# 1604_lora_rak811.net
KiCad netlist of a schematic drawn in EAGLE
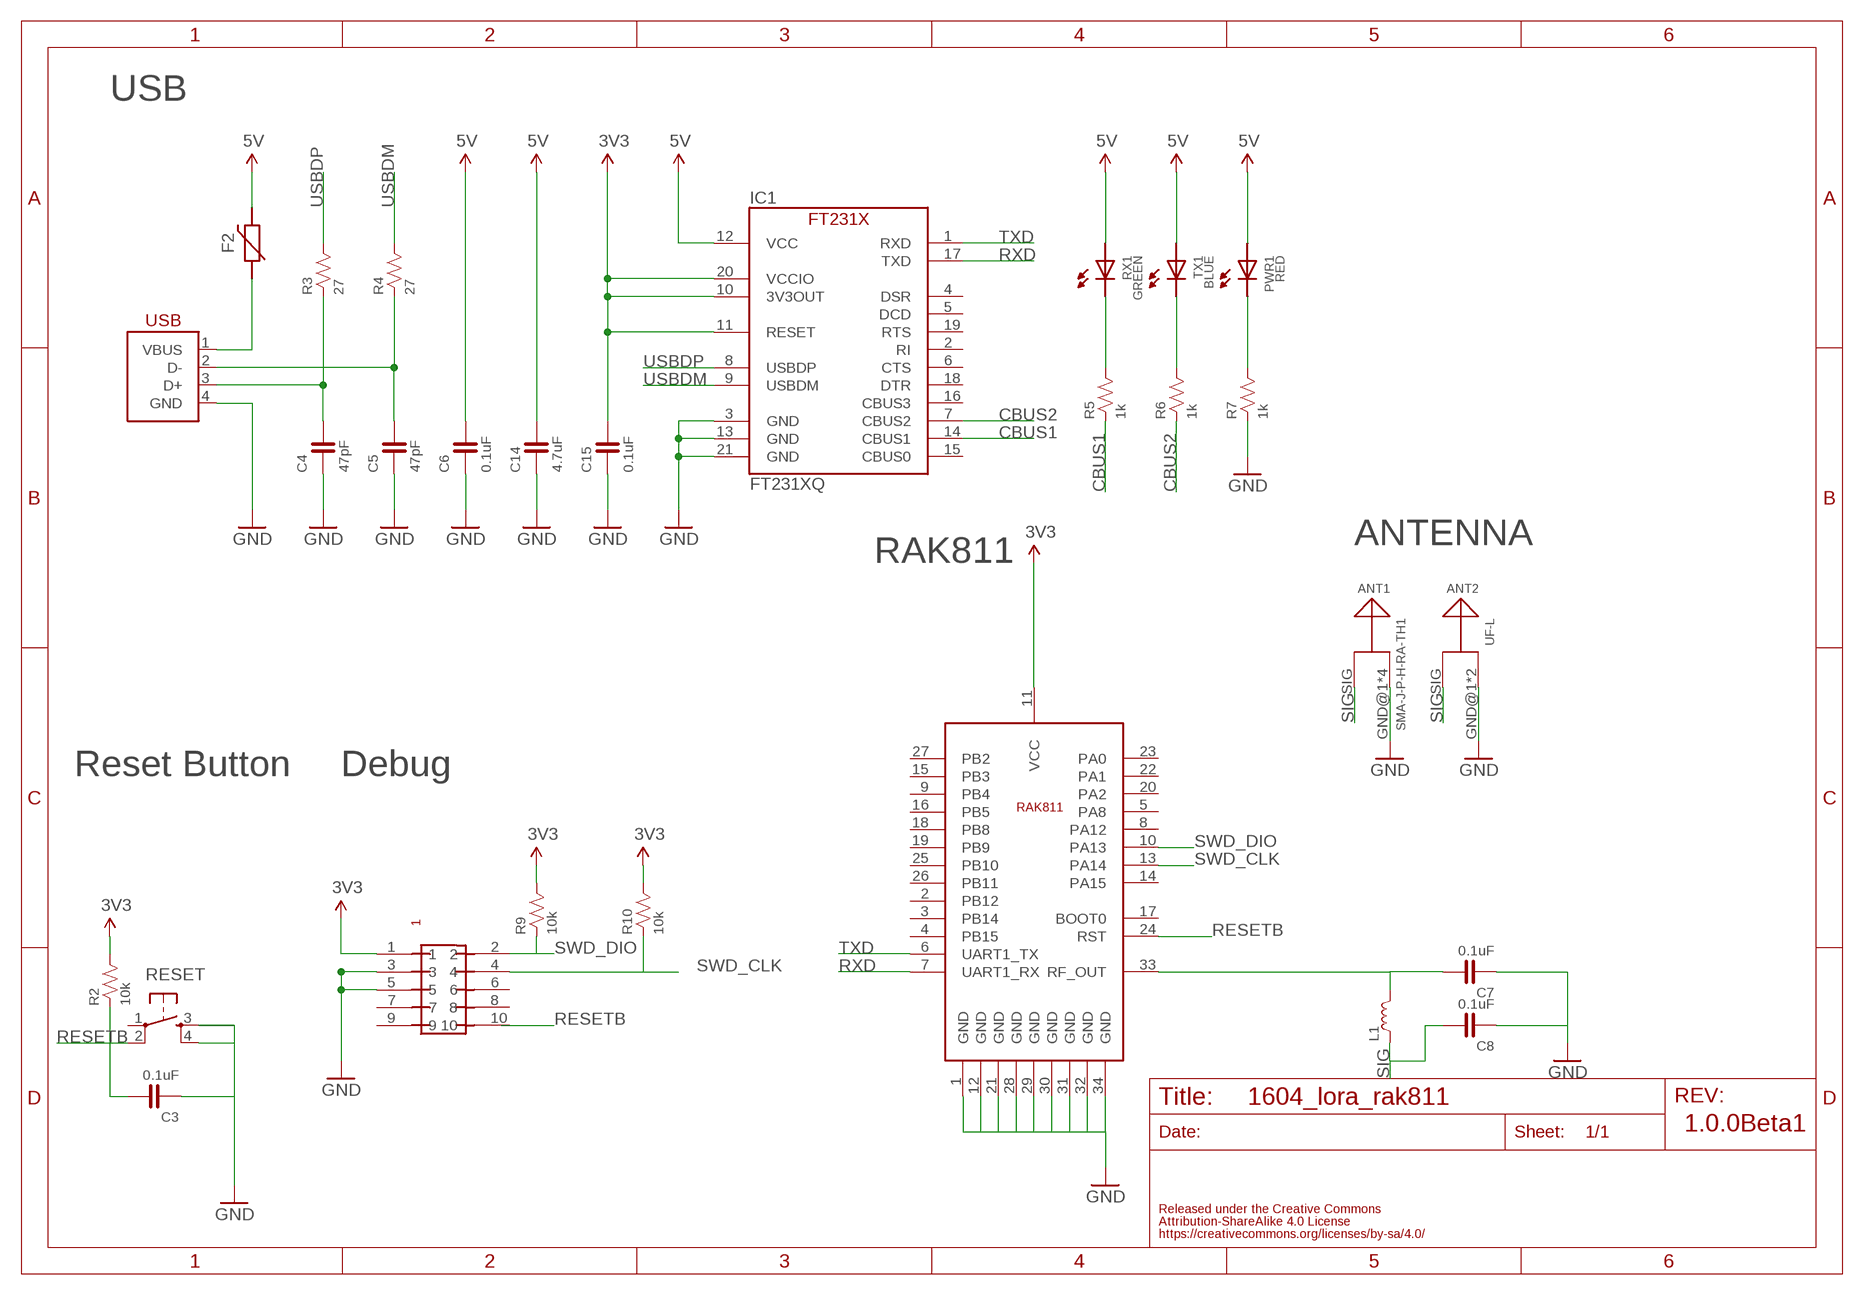
[diagram p0: schematic, sheet 1]

(export (version "E")
  (design (tool "Eeschema 10.0.6"))
  (components
    (comp (ref "ANT1")
      (value "SMA-J-P-H-RA-TH1")
      (footprint "eagle-import:SMA–J–P–H–RA–TH1")
      (libsource (lib "eagle-import") (part "ANTENA_SMA-J-P-H-RA-TH1"))
    )
    (comp (ref "ANT2")
      (value "UF-L")
      (footprint "eagle-import:HIROSE-UF-L")
      (libsource (lib "eagle-import") (part "ANTENA_HIROSE-UF-L"))
    )
    (comp (ref "C3")
      (value "0.1uF")
      (footprint "eagle-import:0603-NARROW")
      (libsource (lib "eagle-import") (part "CAPACITOR-0603_NARROW"))
    )
    (comp (ref "C4")
      (value "47pF")
      (footprint "eagle-import:0603-NARROW")
      (libsource (lib "eagle-import") (part "CAPACITOR-0603_NARROW"))
    )
    (comp (ref "C5")
      (value "47pF")
      (footprint "eagle-import:0603-NARROW")
      (libsource (lib "eagle-import") (part "CAPACITOR-0603_NARROW"))
    )
    (comp (ref "C6")
      (value "0.1uF")
      (footprint "eagle-import:0603-NARROW")
      (libsource (lib "eagle-import") (part "CAPACITOR-0603_NARROW"))
    )
    (comp (ref "C7")
      (value "0.1uF")
      (footprint "eagle-import:0603-NARROW")
      (libsource (lib "eagle-import") (part "CAPACITOR-0603_NARROW"))
    )
    (comp (ref "C8")
      (value "0.1uF")
      (footprint "eagle-import:0603-NARROW")
      (libsource (lib "eagle-import") (part "CAPACITOR-0603_NARROW"))
    )
    (comp (ref "C14")
      (value "4.7uF")
      (footprint "eagle-import:0603-NARROW")
      (libsource (lib "eagle-import") (part "CAPACITOR-0603_NARROW"))
    )
    (comp (ref "C15")
      (value "0.1uF")
      (footprint "eagle-import:0603-NARROW")
      (libsource (lib "eagle-import") (part "CAPACITOR-0603_NARROW"))
    )
    (comp (ref "F2")
      (value "POLYSWITCH")
      (footprint "eagle-import:NANOSMDC035F")
      (libsource (lib "eagle-import") (part "POLYSWITCH"))
    )
    (comp (ref "IC1")
      (value "FT231XQ")
      (footprint "eagle-import:QFN-20_FT231X")
      (libsource (lib "eagle-import") (part "FT231XQ"))
    )
    (comp (ref "L1")
      (value "COIL-0603")
      (footprint "eagle-import:0603")
      (libsource (lib "eagle-import") (part "COIL-0603"))
    )
    (comp (ref "PWR1")
      (value "RED")
      (footprint "eagle-import:0603-NARROW")
      (libsource (lib "eagle-import") (part "LED-0603-NARROW"))
    )
    (comp (ref "R2")
      (value "10k")
      (footprint "eagle-import:0603-NARROW")
      (libsource (lib "eagle-import") (part "RESISTOR-0603-NARROW"))
    )
    (comp (ref "R3")
      (value "27")
      (footprint "eagle-import:0603-NARROW")
      (libsource (lib "eagle-import") (part "RESISTOR-0603-NARROW"))
    )
    (comp (ref "R4")
      (value "27")
      (footprint "eagle-import:0603-NARROW")
      (libsource (lib "eagle-import") (part "RESISTOR-0603-NARROW"))
    )
    (comp (ref "R5")
      (value "1k")
      (footprint "eagle-import:0603-NARROW")
      (libsource (lib "eagle-import") (part "RESISTOR-0603-NARROW"))
    )
    (comp (ref "R6")
      (value "1k")
      (footprint "eagle-import:0603-NARROW")
      (libsource (lib "eagle-import") (part "RESISTOR-0603-NARROW"))
    )
    (comp (ref "R7")
      (value "1k")
      (footprint "eagle-import:0603-NARROW")
      (libsource (lib "eagle-import") (part "RESISTOR-0603-NARROW"))
    )
    (comp (ref "R9")
      (value "10k")
      (footprint "eagle-import:0603-NARROW")
      (libsource (lib "eagle-import") (part "RESISTOR-0603-NARROW"))
    )
    (comp (ref "R10")
      (value "10k")
      (footprint "eagle-import:0603-NARROW")
      (libsource (lib "eagle-import") (part "RESISTOR-0603-NARROW"))
    )
    (comp (ref "RESET")
      (value "TACT-SWITCH-SMD_KMR2")
      (footprint "eagle-import:KMR2")
      (libsource (lib "eagle-import") (part "TACT-SWITCH-SMD_KMR2"))
    )
    (comp (ref "RX1")
      (value "GREEN")
      (footprint "eagle-import:0603-NARROW")
      (libsource (lib "eagle-import") (part "LED-0603-NARROW"))
    )
    (comp (ref "TX1")
      (value "BLUE")
      (footprint "eagle-import:0603-NARROW")
      (libsource (lib "eagle-import") (part "LED-0603-NARROW"))
    )
    (comp (ref "U$2")
      (value "RAK811")
      (footprint "eagle-import:RAK811")
      (libsource (lib "eagle-import") (part "RAK811"))
    )
    (comp (ref "U$8")
      (value "PIN-HEADER-SMT(1.27MM)2X5")
      (footprint "eagle-import:PIN-HEADER-SMT(1.27MM)2X5")
      (libsource (lib "eagle-import") (part "PIN-HEADER-SMT(1.27MM)2X5"))
    )
    (comp (ref "USB1")
      (value "USB-B_PTH")
      (footprint "eagle-import:USB-4AF103BS")
      (libsource (lib "eagle-import") (part "USB-B_PTH"))
    )
  )
  (nets
    (net (code "1") (name "/CBUS1") (class "Default")
      (node (ref "IC1") (pin "14") (pinfunction "CBUS1_14") (pintype "bidirectional"))
      (node (ref "R5") (pin "1") (pinfunction "1_1") (pintype "bidirectional"))
    )
    (net (code "2") (name "/CBUS2") (class "Default")
      (node (ref "IC1") (pin "7") (pinfunction "CBUS2_7") (pintype "bidirectional"))
      (node (ref "R6") (pin "1") (pinfunction "1_1") (pintype "bidirectional"))
    )
    (net (code "3") (name "/RESETB") (class "Default")
      (node (ref "C3") (pin "2") (pinfunction "2_2") (pintype "passive"))
      (node (ref "R2") (pin "1") (pinfunction "1_1") (pintype "bidirectional"))
      (node (ref "RESET") (pin "2") (pinfunction "2_2") (pintype "passive"))
      (node (ref "U$2") (pin "24") (pinfunction "RST_24") (pintype "bidirectional"))
      (node (ref "U$8") (pin "10") (pinfunction "10_10") (pintype "bidirectional"))
    )
    (net (code "4") (name "/RXD") (class "Default")
      (node (ref "IC1") (pin "17") (pinfunction "TXD_17") (pintype "bidirectional"))
      (node (ref "U$2") (pin "7") (pinfunction "UART1_RX_7") (pintype "bidirectional"))
    )
    (net (code "5") (name "/SIG") (class "Default")
      (node (ref "ANT1") (pin "SIG") (pinfunction "SIG_SIG") (pintype "passive"))
      (node (ref "ANT2") (pin "SIG") (pinfunction "SIG_SIG") (pintype "passive"))
      (node (ref "C8") (pin "2") (pinfunction "2_2") (pintype "passive"))
      (node (ref "L1") (pin "1") (pinfunction "1_1") (pintype "bidirectional"))
    )
    (net (code "6") (name "/SWD_CLK") (class "Default")
      (node (ref "R10") (pin "1") (pinfunction "1_1") (pintype "bidirectional"))
      (node (ref "U$2") (pin "13") (pinfunction "PA14_13") (pintype "bidirectional"))
      (node (ref "U$8") (pin "4") (pinfunction "4_4") (pintype "bidirectional"))
    )
    (net (code "7") (name "/SWD_DIO") (class "Default")
      (node (ref "R9") (pin "1") (pinfunction "1_1") (pintype "bidirectional"))
      (node (ref "U$2") (pin "10") (pinfunction "PA13_10") (pintype "bidirectional"))
      (node (ref "U$8") (pin "2") (pinfunction "2_2") (pintype "bidirectional"))
    )
    (net (code "8") (name "/TXD") (class "Default")
      (node (ref "IC1") (pin "1") (pinfunction "RXD_1") (pintype "bidirectional"))
      (node (ref "U$2") (pin "6") (pinfunction "UART1_TX_6") (pintype "bidirectional"))
    )
    (net (code "9") (name "/USBDM") (class "Default")
      (node (ref "IC1") (pin "9") (pinfunction "USBDM_9") (pintype "bidirectional"))
      (node (ref "R4") (pin "2") (pinfunction "2_2") (pintype "bidirectional"))
    )
    (net (code "10") (name "/USBDP") (class "Default")
      (node (ref "IC1") (pin "8") (pinfunction "USBDP_8") (pintype "bidirectional"))
      (node (ref "R3") (pin "2") (pinfunction "2_2") (pintype "bidirectional"))
    )
    (net (code "11") (name "3V3") (class "Default")
      (node (ref "C15") (pin "2") (pinfunction "2_2") (pintype "passive"))
      (node (ref "IC1") (pin "10") (pinfunction "3V3OUT_10") (pintype "bidirectional"))
      (node (ref "IC1") (pin "11") (pinfunction "RESET_11") (pintype "bidirectional"))
      (node (ref "IC1") (pin "20") (pinfunction "VCCIO_20") (pintype "bidirectional"))
      (node (ref "R10") (pin "2") (pinfunction "2_2") (pintype "bidirectional"))
      (node (ref "R2") (pin "2") (pinfunction "2_2") (pintype "bidirectional"))
      (node (ref "R9") (pin "2") (pinfunction "2_2") (pintype "bidirectional"))
      (node (ref "U$2") (pin "11") (pinfunction "VCC_11") (pintype "bidirectional"))
      (node (ref "U$8") (pin "1") (pinfunction "1_1") (pintype "bidirectional"))
    )
    (net (code "12") (name "5V") (class "Default")
      (node (ref "C14") (pin "2") (pinfunction "2_2") (pintype "passive"))
      (node (ref "C6") (pin "2") (pinfunction "2_2") (pintype "passive"))
      (node (ref "F2") (pin "2") (pinfunction "2_2") (pintype "bidirectional"))
      (node (ref "IC1") (pin "12") (pinfunction "VCC_12") (pintype "bidirectional"))
      (node (ref "PWR1") (pin "ANODE") (pinfunction "ANODE_ANODE") (pintype "passive"))
      (node (ref "RX1") (pin "ANODE") (pinfunction "ANODE_ANODE") (pintype "passive"))
      (node (ref "TX1") (pin "ANODE") (pinfunction "ANODE_ANODE") (pintype "passive"))
    )
    (net (code "13") (name "GND") (class "Default")
      (node (ref "ANT1") (pin "GND@1") (pinfunction "GND_GND@1") (pintype "passive"))
      (node (ref "ANT1") (pin "GND@2") (pinfunction "GND_GND@2") (pintype "passive"))
      (node (ref "ANT1") (pin "GND@3") (pinfunction "GND_GND@3") (pintype "passive"))
      (node (ref "ANT1") (pin "GND@4") (pinfunction "GND_GND@4") (pintype "passive"))
      (node (ref "ANT2") (pin "GND@1") (pinfunction "GND_GND@1") (pintype "passive"))
      (node (ref "ANT2") (pin "GND@2") (pinfunction "GND_GND@2") (pintype "passive"))
      (node (ref "C14") (pin "1") (pinfunction "1_1") (pintype "passive"))
      (node (ref "C15") (pin "1") (pinfunction "1_1") (pintype "passive"))
      (node (ref "C3") (pin "1") (pinfunction "1_1") (pintype "passive"))
      (node (ref "C4") (pin "1") (pinfunction "1_1") (pintype "passive"))
      (node (ref "C5") (pin "1") (pinfunction "1_1") (pintype "passive"))
      (node (ref "C6") (pin "1") (pinfunction "1_1") (pintype "passive"))
      (node (ref "C7") (pin "1") (pinfunction "1_1") (pintype "passive"))
      (node (ref "C8") (pin "1") (pinfunction "1_1") (pintype "passive"))
      (node (ref "IC1") (pin "13") (pinfunction "GND_13") (pintype "bidirectional"))
      (node (ref "IC1") (pin "21") (pinfunction "GND_21") (pintype "bidirectional"))
      (node (ref "IC1") (pin "3") (pinfunction "GND_3") (pintype "bidirectional"))
      (node (ref "R7") (pin "1") (pinfunction "1_1") (pintype "bidirectional"))
      (node (ref "RESET") (pin "3") (pinfunction "3_3") (pintype "passive"))
      (node (ref "RESET") (pin "4") (pinfunction "4_4") (pintype "passive"))
      (node (ref "U$2") (pin "1") (pinfunction "GND_1") (pintype "bidirectional"))
      (node (ref "U$2") (pin "12") (pinfunction "GND_12") (pintype "bidirectional"))
      (node (ref "U$2") (pin "21") (pinfunction "GND_21") (pintype "bidirectional"))
      (node (ref "U$2") (pin "28") (pinfunction "GND_28") (pintype "bidirectional"))
      (node (ref "U$2") (pin "29") (pinfunction "GND_29") (pintype "bidirectional"))
      (node (ref "U$2") (pin "30") (pinfunction "GND_30") (pintype "bidirectional"))
      (node (ref "U$2") (pin "31") (pinfunction "GND_31") (pintype "bidirectional"))
      (node (ref "U$2") (pin "32") (pinfunction "GND_32") (pintype "bidirectional"))
      (node (ref "U$2") (pin "34") (pinfunction "GND_34") (pintype "bidirectional"))
      (node (ref "U$8") (pin "3") (pinfunction "3_3") (pintype "bidirectional"))
      (node (ref "U$8") (pin "5") (pinfunction "5_5") (pintype "bidirectional"))
      (node (ref "USB1") (pin "4") (pinfunction "GND_4") (pintype "bidirectional"))
    )
    (net (code "14") (name "Net-(PWR1-PadCATHODE)") (class "Default")
      (node (ref "PWR1") (pin "CATHODE") (pinfunction "CATHODE_CATHODE") (pintype "passive"))
      (node (ref "R7") (pin "2") (pinfunction "2_2") (pintype "bidirectional"))
    )
    (net (code "15") (name "Net-(R5-Pad2)") (class "Default")
      (node (ref "R5") (pin "2") (pinfunction "2_2") (pintype "bidirectional"))
      (node (ref "RX1") (pin "CATHODE") (pinfunction "CATHODE_CATHODE") (pintype "passive"))
    )
    (net (code "16") (name "Net-(R6-Pad2)") (class "Default")
      (node (ref "R6") (pin "2") (pinfunction "2_2") (pintype "bidirectional"))
      (node (ref "TX1") (pin "CATHODE") (pinfunction "CATHODE_CATHODE") (pintype "passive"))
    )
    (net (code "17") (name "Net-(U$2-RF_OUT)") (class "Default")
      (node (ref "C7") (pin "2") (pinfunction "2_2") (pintype "passive"))
      (node (ref "L1") (pin "2") (pinfunction "2_2") (pintype "bidirectional"))
      (node (ref "U$2") (pin "33") (pinfunction "RF_OUT_33") (pintype "bidirectional"))
    )
    (net (code "18") (name "Net-(USB1-D+)") (class "Default")
      (node (ref "C4") (pin "2") (pinfunction "2_2") (pintype "passive"))
      (node (ref "R3") (pin "1") (pinfunction "1_1") (pintype "bidirectional"))
      (node (ref "USB1") (pin "3") (pinfunction "D+_3") (pintype "bidirectional"))
    )
    (net (code "19") (name "Net-(USB1-D-)") (class "Default")
      (node (ref "C5") (pin "2") (pinfunction "2_2") (pintype "passive"))
      (node (ref "R4") (pin "1") (pinfunction "1_1") (pintype "bidirectional"))
      (node (ref "USB1") (pin "2") (pinfunction "D-_2") (pintype "bidirectional"))
    )
    (net (code "20") (name "Net-(USB1-VBUS)") (class "Default")
      (node (ref "F2") (pin "1") (pinfunction "1_1") (pintype "bidirectional"))
      (node (ref "USB1") (pin "1") (pinfunction "VBUS_1") (pintype "bidirectional"))
    )
    (net (code "21") (name "unconnected-(IC1-CBUS0-Pad15)") (class "Default")
      (node (ref "IC1") (pin "15") (pinfunction "CBUS0_15") (pintype "bidirectional"))
    )
    (net (code "22") (name "unconnected-(IC1-CBUS3-Pad16)") (class "Default")
      (node (ref "IC1") (pin "16") (pinfunction "CBUS3_16") (pintype "bidirectional"))
    )
    (net (code "23") (name "unconnected-(IC1-CTS-Pad6)") (class "Default")
      (node (ref "IC1") (pin "6") (pinfunction "CTS_6") (pintype "bidirectional"))
    )
    (net (code "24") (name "unconnected-(IC1-DCD-Pad5)") (class "Default")
      (node (ref "IC1") (pin "5") (pinfunction "DCD_5") (pintype "bidirectional"))
    )
    (net (code "25") (name "unconnected-(IC1-DSR-Pad4)") (class "Default")
      (node (ref "IC1") (pin "4") (pinfunction "DSR_4") (pintype "bidirectional"))
    )
    (net (code "26") (name "unconnected-(IC1-DTR-Pad18)") (class "Default")
      (node (ref "IC1") (pin "18") (pinfunction "DTR_18") (pintype "bidirectional"))
    )
    (net (code "27") (name "unconnected-(IC1-RI-Pad2)") (class "Default")
      (node (ref "IC1") (pin "2") (pinfunction "RI_2") (pintype "bidirectional"))
    )
    (net (code "28") (name "unconnected-(IC1-RTS-Pad19)") (class "Default")
      (node (ref "IC1") (pin "19") (pinfunction "RTS_19") (pintype "bidirectional"))
    )
    (net (code "29") (name "unconnected-(RESET-Pad1)") (class "Default")
      (node (ref "RESET") (pin "1") (pinfunction "1_1") (pintype "passive"))
    )
    (net (code "30") (name "unconnected-(U$2-BOOT0-Pad17)") (class "Default")
      (node (ref "U$2") (pin "17") (pinfunction "BOOT0_17") (pintype "bidirectional"))
    )
    (net (code "31") (name "unconnected-(U$2-PA0-Pad23)") (class "Default")
      (node (ref "U$2") (pin "23") (pinfunction "PA0_23") (pintype "bidirectional"))
    )
    (net (code "32") (name "unconnected-(U$2-PA1-Pad22)") (class "Default")
      (node (ref "U$2") (pin "22") (pinfunction "PA1_22") (pintype "bidirectional"))
    )
    (net (code "33") (name "unconnected-(U$2-PA2-Pad20)") (class "Default")
      (node (ref "U$2") (pin "20") (pinfunction "PA2_20") (pintype "bidirectional"))
    )
    (net (code "34") (name "unconnected-(U$2-PA8-Pad5)") (class "Default")
      (node (ref "U$2") (pin "5") (pinfunction "PA8_5") (pintype "bidirectional"))
    )
    (net (code "35") (name "unconnected-(U$2-PA12-Pad8)") (class "Default")
      (node (ref "U$2") (pin "8") (pinfunction "PA12_8") (pintype "bidirectional"))
    )
    (net (code "36") (name "unconnected-(U$2-PA15-Pad14)") (class "Default")
      (node (ref "U$2") (pin "14") (pinfunction "PA15_14") (pintype "bidirectional"))
    )
    (net (code "37") (name "unconnected-(U$2-PB2-Pad27)") (class "Default")
      (node (ref "U$2") (pin "27") (pinfunction "PB2_27") (pintype "bidirectional"))
    )
    (net (code "38") (name "unconnected-(U$2-PB3-Pad15)") (class "Default")
      (node (ref "U$2") (pin "15") (pinfunction "PB3_15") (pintype "bidirectional"))
    )
    (net (code "39") (name "unconnected-(U$2-PB4-Pad9)") (class "Default")
      (node (ref "U$2") (pin "9") (pinfunction "PB4_9") (pintype "bidirectional"))
    )
    (net (code "40") (name "unconnected-(U$2-PB5-Pad16)") (class "Default")
      (node (ref "U$2") (pin "16") (pinfunction "PB5_16") (pintype "bidirectional"))
    )
    (net (code "41") (name "unconnected-(U$2-PB8-Pad18)") (class "Default")
      (node (ref "U$2") (pin "18") (pinfunction "PB8_18") (pintype "bidirectional"))
    )
    (net (code "42") (name "unconnected-(U$2-PB9-Pad19)") (class "Default")
      (node (ref "U$2") (pin "19") (pinfunction "PB9_19") (pintype "bidirectional"))
    )
    (net (code "43") (name "unconnected-(U$2-PB10-Pad25)") (class "Default")
      (node (ref "U$2") (pin "25") (pinfunction "PB10_25") (pintype "bidirectional"))
    )
    (net (code "44") (name "unconnected-(U$2-PB11-Pad26)") (class "Default")
      (node (ref "U$2") (pin "26") (pinfunction "PB11_26") (pintype "bidirectional"))
    )
    (net (code "45") (name "unconnected-(U$2-PB12-Pad2)") (class "Default")
      (node (ref "U$2") (pin "2") (pinfunction "PB12_2") (pintype "bidirectional"))
    )
    (net (code "46") (name "unconnected-(U$2-PB14-Pad3)") (class "Default")
      (node (ref "U$2") (pin "3") (pinfunction "PB14_3") (pintype "bidirectional"))
    )
    (net (code "47") (name "unconnected-(U$2-PB15-Pad4)") (class "Default")
      (node (ref "U$2") (pin "4") (pinfunction "PB15_4") (pintype "bidirectional"))
    )
    (net (code "48") (name "unconnected-(U$8-Pad6)") (class "Default")
      (node (ref "U$8") (pin "6") (pinfunction "6_6") (pintype "bidirectional"))
    )
    (net (code "49") (name "unconnected-(U$8-Pad7)") (class "Default")
      (node (ref "U$8") (pin "7") (pinfunction "7_7") (pintype "bidirectional"))
    )
    (net (code "50") (name "unconnected-(U$8-Pad8)") (class "Default")
      (node (ref "U$8") (pin "8") (pinfunction "8_8") (pintype "bidirectional"))
    )
    (net (code "51") (name "unconnected-(U$8-Pad9)") (class "Default")
      (node (ref "U$8") (pin "9") (pinfunction "9_9") (pintype "bidirectional"))
    )
  )
)
